# Radio.net
KiCad netlist of a schematic drawn in Altium Designer
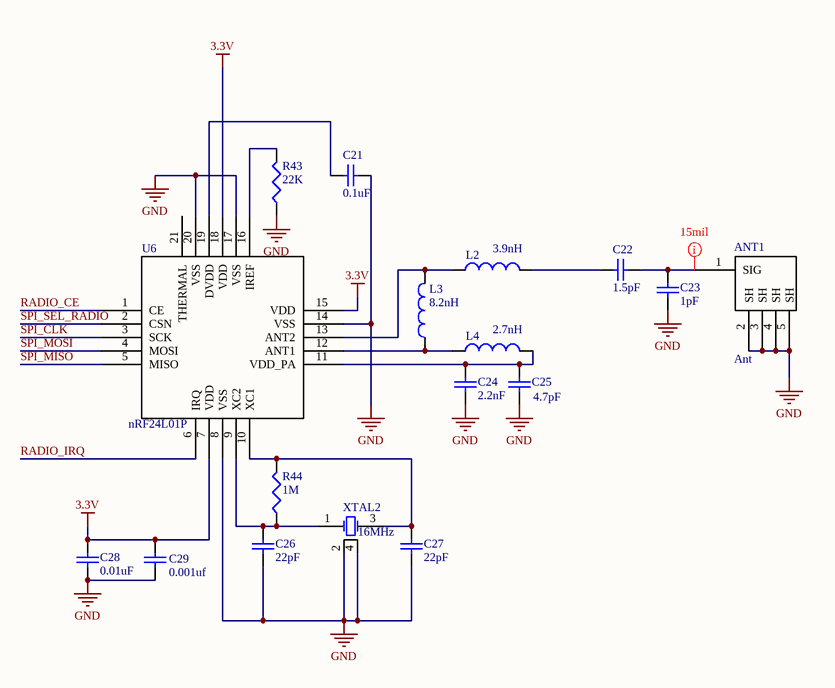
[diagram p0: Radio.SchDoc]

(export (version "E")
  (design (tool "Eeschema 10.0.6"))
  (components
    (comp (ref "ANT1") (value "Ant") (footprint "AntennaSMA") (libsource (lib "mrone") (part "AntennaConn")))
    (comp (ref "C21")
      (value "0.1uF")
      (footprint "CAPC1005L")
      (description "Capacitor (Semiconductor SIM Model)")
      (fields (field (name "Comment") "Cap Semi") (field (name "PUBLISHER") "Altium Limited"))
      (libsource (lib "Miscellaneous Devices") (part "Cap Semi"))
    )
    (comp (ref "C22")
      (value "1.5pF")
      (footprint "CAPC1005L")
      (description "Capacitor (Semiconductor SIM Model)")
      (fields (field (name "Comment") "Cap Semi") (field (name "PUBLISHER") "Altium Limited"))
      (libsource (lib "Miscellaneous Devices") (part "Cap Semi"))
    )
    (comp (ref "C23")
      (value "1pF")
      (footprint "CAPC1005L")
      (description "Capacitor (Semiconductor SIM Model)")
      (fields (field (name "Comment") "Cap Semi") (field (name "PUBLISHER") "Altium Limited"))
      (libsource (lib "Miscellaneous Devices") (part "Cap Semi"))
    )
    (comp (ref "C24")
      (value "2.2nF")
      (footprint "CAPC1005L")
      (description "Capacitor (Semiconductor SIM Model)")
      (fields (field (name "Comment") "Cap Semi") (field (name "PUBLISHER") "Altium Limited"))
      (libsource (lib "Miscellaneous Devices") (part "Cap Semi"))
    )
    (comp (ref "C25")
      (value "4.7pF")
      (footprint "CAPC1005L")
      (description "Capacitor (Semiconductor SIM Model)")
      (fields (field (name "Comment") "Cap Semi") (field (name "PUBLISHER") "Altium Limited"))
      (libsource (lib "Miscellaneous Devices") (part "Cap Semi"))
    )
    (comp (ref "C26")
      (value "22pF")
      (footprint "CAPC1005L")
      (description "Capacitor (Semiconductor SIM Model)")
      (fields (field (name "Comment") "Cap Semi") (field (name "PUBLISHER") "Altium Limited"))
      (libsource (lib "Miscellaneous Devices") (part "Cap Semi"))
    )
    (comp (ref "C27")
      (value "22pF")
      (footprint "CAPC1005L")
      (description "Capacitor (Semiconductor SIM Model)")
      (fields (field (name "Comment") "Cap Semi") (field (name "PUBLISHER") "Altium Limited"))
      (libsource (lib "Miscellaneous Devices") (part "Cap Semi"))
    )
    (comp (ref "C28")
      (value "0.01uF")
      (footprint "CAPC1005L")
      (description "Capacitor (Semiconductor SIM Model)")
      (fields (field (name "Comment") "Cap Semi") (field (name "PUBLISHER") "Altium Limited"))
      (libsource (lib "Miscellaneous Devices") (part "Cap Semi"))
    )
    (comp (ref "C29")
      (value "0.001uf")
      (footprint "CAPC1005L")
      (description "Capacitor (Semiconductor SIM Model)")
      (fields (field (name "Comment") "Cap Semi") (field (name "PUBLISHER") "Altium Limited"))
      (libsource (lib "Miscellaneous Devices") (part "Cap Semi"))
    )
    (comp (ref "L2")
      (value "3.9nH")
      (footprint "INDC1005AL")
      (description "Inductor")
      (fields (field (name "PUBLISHER") "Altium Limited"))
      (libsource (lib "Miscellaneous Devices") (part "Inductor"))
    )
    (comp (ref "L3")
      (value "8.2nH")
      (footprint "INDC1005AL")
      (description "Inductor")
      (fields (field (name "PUBLISHER") "Altium Limited"))
      (libsource (lib "Miscellaneous Devices") (part "Inductor"))
    )
    (comp (ref "L4")
      (value "2.7nH")
      (footprint "INDC1005AL")
      (description "Inductor")
      (fields (field (name "PUBLISHER") "Altium Limited"))
      (libsource (lib "Miscellaneous Devices") (part "Inductor"))
    )
    (comp (ref "R43")
      (value "22K")
      (footprint "RESC1608L")
      (description "Resistor")
      (fields (field (name "Comment") "Res3") (field (name "PUBLISHER") "Altium Limited"))
      (libsource (lib "Miscellaneous Devices") (part "Res3"))
    )
    (comp (ref "R44")
      (value "1M")
      (footprint "RESC1608L")
      (description "Resistor")
      (fields (field (name "Comment") "Res3") (field (name "PUBLISHER") "Altium Limited"))
      (libsource (lib "Miscellaneous Devices") (part "Res3"))
    )
    (comp (ref "U6")
      (value "nRF24L01P")
      (footprint "QFN-20")
      (libsource (lib "mrone") (part "radio-nRF24L01P"))
    )
    (comp (ref "XTAL2") (value "16MHz") (footprint "CRYSTAL") (libsource (lib "mrone") (part "Crystal")))
  )
  (nets
    (net (code "1") (name "/RADIO_CE") (class "Default")
      (node (ref "U6") (pin "1") (pinfunction "CE_1") (pintype "passive"))
    )
    (net (code "2") (name "/RADIO_IRQ") (class "Default")
      (node (ref "U6") (pin "6") (pinfunction "IRQ_6") (pintype "passive"))
    )
    (net (code "3") (name "/SPI_CLK") (class "Default")
      (node (ref "U6") (pin "3") (pinfunction "SCK_3") (pintype "passive"))
    )
    (net (code "4") (name "/SPI_MISO") (class "Default")
      (node (ref "U6") (pin "5") (pinfunction "MISO_5") (pintype "passive"))
    )
    (net (code "5") (name "/SPI_MOSI") (class "Default")
      (node (ref "U6") (pin "4") (pinfunction "MOSI_4") (pintype "passive"))
    )
    (net (code "6") (name "/SPI_SEL_RADIO") (class "Default")
      (node (ref "U6") (pin "2") (pinfunction "CSN_2") (pintype "passive"))
    )
    (net (code "7") (name "3.3V") (class "Default")
      (node (ref "C28") (pin "2") (pinfunction "2_2") (pintype "passive"))
      (node (ref "C29") (pin "2") (pinfunction "2_2") (pintype "passive"))
      (node (ref "U6") (pin "15") (pinfunction "VDD_15") (pintype "passive"))
      (node (ref "U6") (pin "18") (pinfunction "VDD_18") (pintype "passive"))
      (node (ref "U6") (pin "7") (pinfunction "VDD_7") (pintype "passive"))
    )
    (net (code "8") (name "GND") (class "Default")
      (node (ref "ANT1") (pin "2") (pinfunction "SH_2") (pintype "passive"))
      (node (ref "ANT1") (pin "3") (pinfunction "SH_3") (pintype "passive"))
      (node (ref "ANT1") (pin "4") (pinfunction "SH_4") (pintype "passive"))
      (node (ref "ANT1") (pin "5") (pinfunction "SH_5") (pintype "passive"))
      (node (ref "C21") (pin "1") (pinfunction "1_1") (pintype "passive"))
      (node (ref "C23") (pin "1") (pinfunction "1_1") (pintype "passive"))
      (node (ref "C24") (pin "1") (pinfunction "1_1") (pintype "passive"))
      (node (ref "C25") (pin "1") (pinfunction "1_1") (pintype "passive"))
      (node (ref "C26") (pin "1") (pinfunction "1_1") (pintype "passive"))
      (node (ref "C27") (pin "1") (pinfunction "1_1") (pintype "passive"))
      (node (ref "C28") (pin "1") (pinfunction "1_1") (pintype "passive"))
      (node (ref "C29") (pin "1") (pinfunction "1_1") (pintype "passive"))
      (node (ref "R43") (pin "1") (pinfunction "1_1") (pintype "passive"))
      (node (ref "U6") (pin "14") (pinfunction "VSS_14") (pintype "passive"))
      (node (ref "U6") (pin "17") (pinfunction "VSS_17") (pintype "passive"))
      (node (ref "U6") (pin "20") (pinfunction "VSS_20") (pintype "passive"))
      (node (ref "U6") (pin "8") (pinfunction "VSS_8") (pintype "passive"))
      (node (ref "XTAL2") (pin "2") (pinfunction "GND_2") (pintype "passive"))
      (node (ref "XTAL2") (pin "4") (pinfunction "GND_4") (pintype "passive"))
    )
    (net (code "9") (name "Net-(ANT1-SIG)") (class "Default")
      (node (ref "ANT1") (pin "1") (pinfunction "SIG_1") (pintype "passive"))
      (node (ref "C22") (pin "1") (pinfunction "1_1") (pintype "passive"))
      (node (ref "C23") (pin "2") (pinfunction "2_2") (pintype "passive"))
    )
    (net (code "10") (name "Net-(C22-Pad2)") (class "Default")
      (node (ref "C22") (pin "2") (pinfunction "2_2") (pintype "passive"))
      (node (ref "L2") (pin "2") (pinfunction "2_2") (pintype "passive"))
    )
    (net (code "11") (name "Net-(U6-ANT1)") (class "Default")
      (node (ref "L3") (pin "1") (pinfunction "1_1") (pintype "passive"))
      (node (ref "L4") (pin "1") (pinfunction "1_1") (pintype "passive"))
      (node (ref "U6") (pin "12") (pinfunction "ANT1_12") (pintype "passive"))
    )
    (net (code "12") (name "Net-(U6-ANT2)") (class "Default")
      (node (ref "L2") (pin "1") (pinfunction "1_1") (pintype "passive"))
      (node (ref "L3") (pin "2") (pinfunction "2_2") (pintype "passive"))
      (node (ref "U6") (pin "13") (pinfunction "ANT2_13") (pintype "passive"))
    )
    (net (code "13") (name "Net-(U6-DVDD)") (class "Default")
      (node (ref "C21") (pin "2") (pinfunction "2_2") (pintype "passive"))
      (node (ref "U6") (pin "19") (pinfunction "DVDD_19") (pintype "passive"))
    )
    (net (code "14") (name "Net-(U6-IREF)") (class "Default")
      (node (ref "R43") (pin "2") (pinfunction "2_2") (pintype "passive"))
      (node (ref "U6") (pin "16") (pinfunction "IREF_16") (pintype "passive"))
    )
    (net (code "15") (name "Net-(U6-VDD_PA)") (class "Default")
      (node (ref "C24") (pin "2") (pinfunction "2_2") (pintype "passive"))
      (node (ref "C25") (pin "2") (pinfunction "2_2") (pintype "passive"))
      (node (ref "L4") (pin "2") (pinfunction "2_2") (pintype "passive"))
      (node (ref "U6") (pin "11") (pinfunction "VDD_PA_11") (pintype "passive"))
    )
    (net (code "16") (name "Net-(U6-XC1)") (class "Default")
      (node (ref "C27") (pin "2") (pinfunction "2_2") (pintype "passive"))
      (node (ref "R44") (pin "2") (pinfunction "2_2") (pintype "passive"))
      (node (ref "U6") (pin "10") (pinfunction "XC1_10") (pintype "passive"))
      (node (ref "XTAL2") (pin "3") (pinfunction "OSC2_3") (pintype "passive"))
    )
    (net (code "17") (name "Net-(U6-XC2)") (class "Default")
      (node (ref "C26") (pin "2") (pinfunction "2_2") (pintype "passive"))
      (node (ref "R44") (pin "1") (pinfunction "1_1") (pintype "passive"))
      (node (ref "U6") (pin "9") (pinfunction "XC2_9") (pintype "passive"))
      (node (ref "XTAL2") (pin "1") (pinfunction "OSC1_1") (pintype "passive"))
    )
    (net (code "18") (name "unconnected-(U6-THERMAL-Pad21)") (class "Default")
      (node (ref "U6") (pin "21") (pinfunction "THERMAL_21") (pintype "passive"))
    )
  )
)
